# BEACON.net
KiCad netlist of a schematic drawn in EAGLE
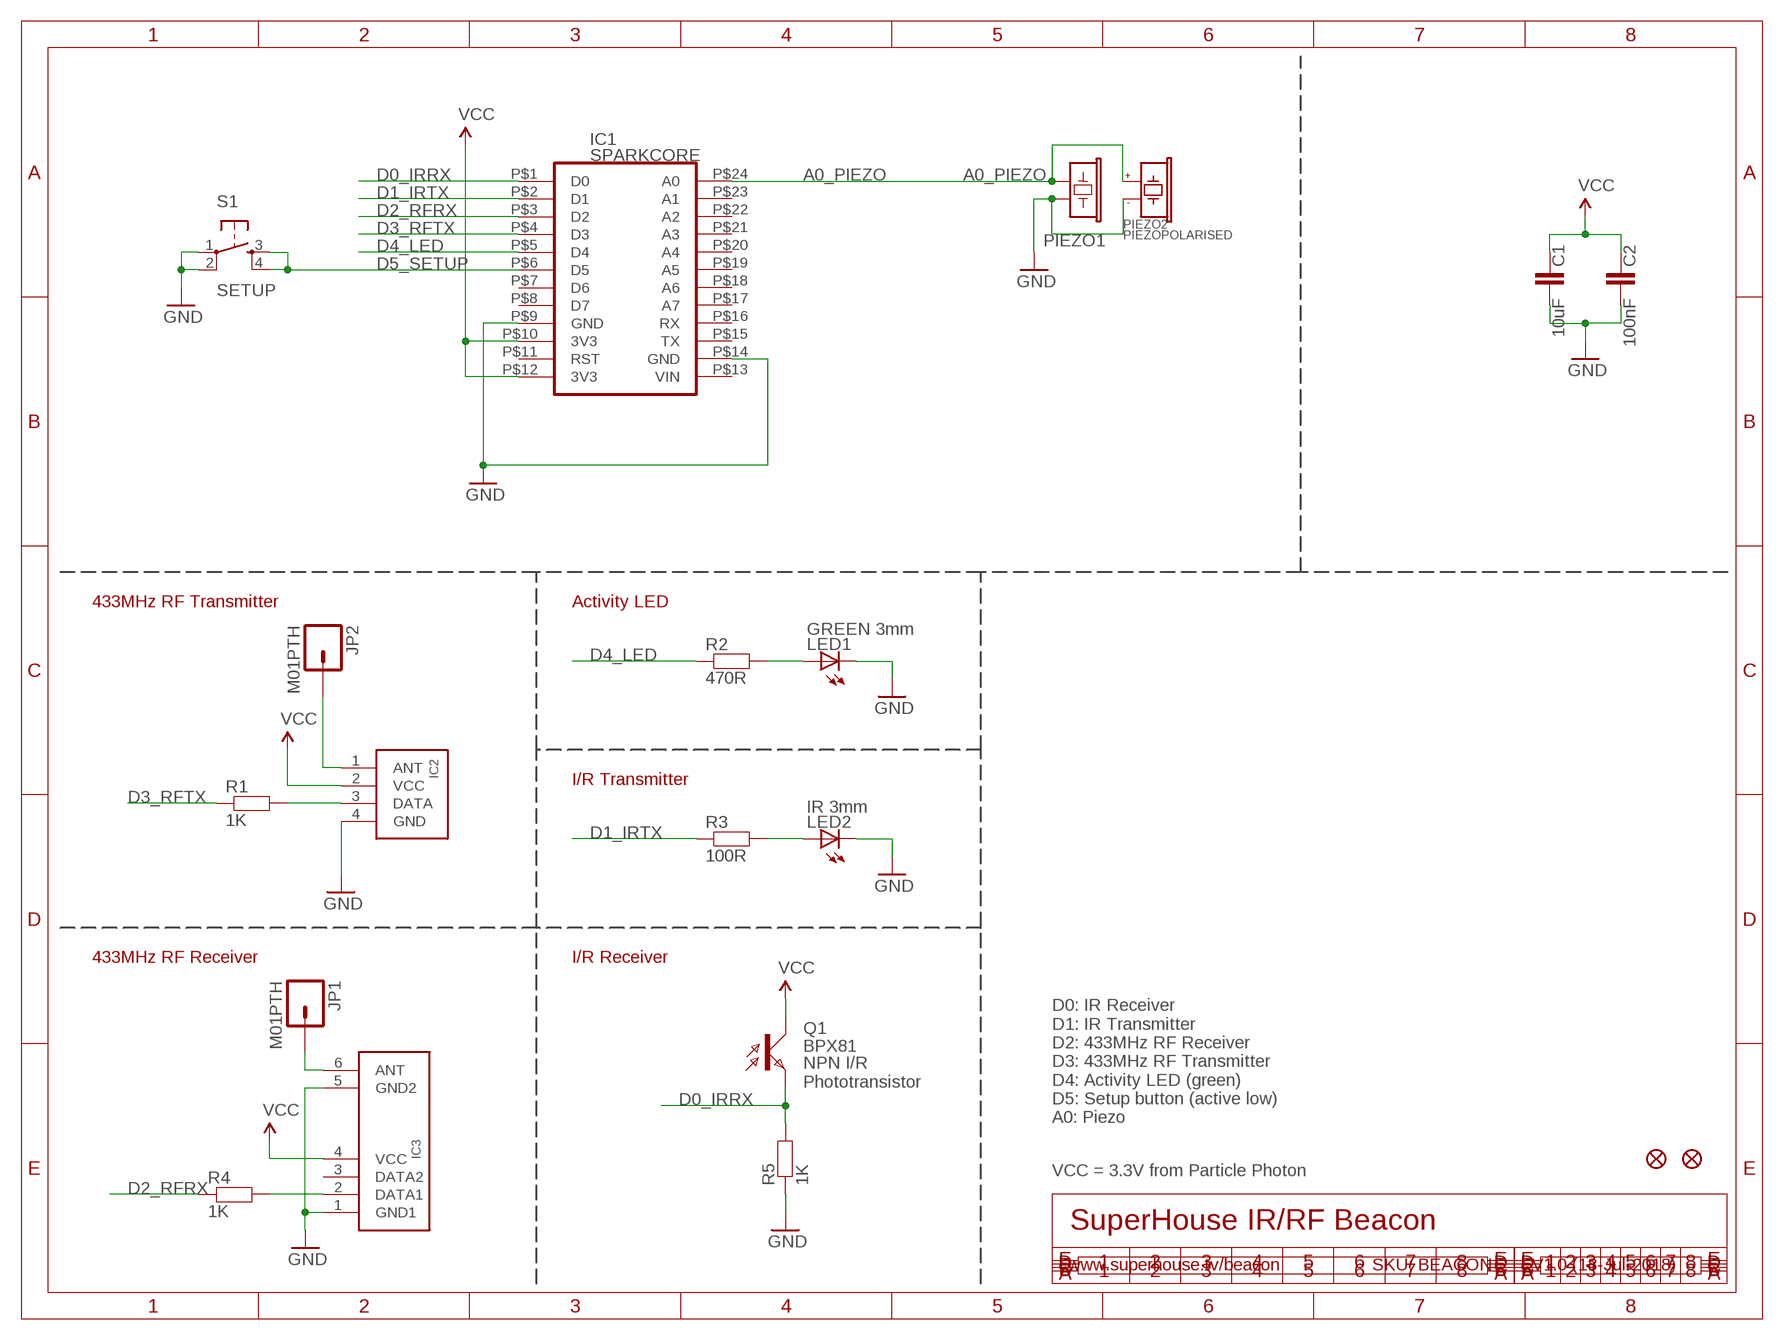
[diagram p0: schematic, sheet 1]

(export (version "E")
  (design (tool "Eeschema 10.0.6"))
  (components
    (comp (ref "C1")
      (value "10uF")
      (footprint "eagle-import:C0805")
      (libsource (lib "eagle-import") (part "C-EUC0805"))
    )
    (comp (ref "C2")
      (value "100nF")
      (footprint "eagle-import:0603")
      (libsource (lib "eagle-import") (part "CAP0603"))
    )
    (comp (ref "IC1")
      (value "SPARKCORE")
      (footprint "eagle-import:SPARKCORE")
      (libsource (lib "eagle-import") (part "SPARKCORE"))
    )
    (comp (ref "IC2")
      (value "TX-C1FLAT")
      (footprint "eagle-import:TX-C1-FLAT")
      (libsource (lib "eagle-import") (part "TX-C1FLAT"))
    )
    (comp (ref "IC3")
      (value "RXB1SHORTFLAT")
      (footprint "eagle-import:RX-B1-SHORT-FLAT")
      (libsource (lib "eagle-import") (part "RXB1SHORTFLAT"))
    )
    (comp (ref "JP1")
      (value "M01PTH")
      (footprint "eagle-import:1X01")
      (libsource (lib "eagle-import") (part "M01PTH"))
    )
    (comp (ref "JP2")
      (value "M01PTH")
      (footprint "eagle-import:1X01")
      (libsource (lib "eagle-import") (part "M01PTH"))
    )
    (comp (ref "LED1")
      (value "GREEN 3mm")
      (footprint "eagle-import:LED3MM")
      (libsource (lib "eagle-import") (part "LED3MM"))
    )
    (comp (ref "LED2")
      (value "IR 3mm")
      (footprint "eagle-import:LED3MM")
      (libsource (lib "eagle-import") (part "LED3MM"))
    )
    (comp (ref "PIEZO1")
      (value "BUZZERSMD12X12")
      (footprint "eagle-import:BUZZER-12X12-SMT")
      (libsource (lib "eagle-import") (part "BUZZERSMD12X12"))
    )
    (comp (ref "PIEZO2")
      (value "PIEZOPOLARISED")
      (footprint "eagle-import:PIEZO12MMWIDEPOLARISED")
      (libsource (lib "eagle-import") (part "PIEZOPOLARISED"))
    )
    (comp (ref "Q1")
      (value "BPX81")
      (footprint "eagle-import:BPX81")
      (libsource (lib "eagle-import") (part "BPX81"))
    )
    (comp (ref "R1")
      (value "1K")
      (footprint "eagle-import:0603")
      (libsource (lib "eagle-import") (part "RESISTOR0603"))
    )
    (comp (ref "R2")
      (value "470R")
      (footprint "eagle-import:0603")
      (libsource (lib "eagle-import") (part "RESISTOR0603"))
    )
    (comp (ref "R3")
      (value "100R")
      (footprint "eagle-import:0603")
      (libsource (lib "eagle-import") (part "RESISTOR0603"))
    )
    (comp (ref "R4")
      (value "1K")
      (footprint "eagle-import:0603")
      (libsource (lib "eagle-import") (part "RESISTOR0603"))
    )
    (comp (ref "R5")
      (value "1K")
      (footprint "eagle-import:0603")
      (libsource (lib "eagle-import") (part "RESISTOR0603"))
    )
    (comp (ref "S1")
      (value "SETUP")
      (footprint "eagle-import:TACTILE-PTH")
      (libsource (lib "eagle-import") (part "TAC_SWITCHPTH"))
    )
    (comp (ref "U$4")
      (value "FIDUCIAL1X2.5")
      (footprint "eagle-import:FIDUCIAL-1X2.5")
      (libsource (lib "eagle-import") (part "FIDUCIAL1X2.5"))
    )
    (comp (ref "U$5")
      (value "FIDUCIAL1X2.5")
      (footprint "eagle-import:FIDUCIAL-1X2.5")
      (libsource (lib "eagle-import") (part "FIDUCIAL1X2.5"))
    )
  )
  (nets
    (net (code "1") (name "/A0_PIEZO") (class "Default")
      (node (ref "IC1") (pin "P$24") (pinfunction "A0_P$24") (pintype "bidirectional"))
      (node (ref "PIEZO1") (pin "1") (pinfunction "1_1") (pintype "passive"))
      (node (ref "PIEZO2") (pin "1") (pinfunction "+_1") (pintype "bidirectional"))
    )
    (net (code "2") (name "/D0_IRRX") (class "Default")
      (node (ref "IC1") (pin "P$1") (pinfunction "D0_P$1") (pintype "bidirectional"))
      (node (ref "Q1") (pin "E") (pinfunction "E_E") (pintype "passive"))
      (node (ref "R5") (pin "2") (pinfunction "2_2") (pintype "passive"))
    )
    (net (code "3") (name "/D1_IRTX") (class "Default")
      (node (ref "IC1") (pin "P$2") (pinfunction "D1_P$2") (pintype "bidirectional"))
      (node (ref "R3") (pin "1") (pinfunction "1_1") (pintype "passive"))
    )
    (net (code "4") (name "/D2_RFRX") (class "Default")
      (node (ref "IC1") (pin "P$3") (pinfunction "D2_P$3") (pintype "bidirectional"))
      (node (ref "R4") (pin "1") (pinfunction "1_1") (pintype "passive"))
    )
    (net (code "5") (name "/D3_RFTX") (class "Default")
      (node (ref "IC1") (pin "P$4") (pinfunction "D3_P$4") (pintype "bidirectional"))
      (node (ref "R1") (pin "1") (pinfunction "1_1") (pintype "passive"))
    )
    (net (code "6") (name "/D4_LED") (class "Default")
      (node (ref "IC1") (pin "P$5") (pinfunction "D4_P$5") (pintype "bidirectional"))
      (node (ref "R2") (pin "1") (pinfunction "1_1") (pintype "passive"))
    )
    (net (code "7") (name "/D5_SETUP") (class "Default")
      (node (ref "IC1") (pin "P$6") (pinfunction "D5_P$6") (pintype "bidirectional"))
      (node (ref "S1") (pin "3") (pinfunction "3_3") (pintype "passive"))
      (node (ref "S1") (pin "4") (pinfunction "4_4") (pintype "passive"))
    )
    (net (code "8") (name "GND") (class "Default")
      (node (ref "C1") (pin "1") (pinfunction "1_1") (pintype "passive"))
      (node (ref "C2") (pin "2") (pinfunction "2_2") (pintype "passive"))
      (node (ref "IC1") (pin "P$14") (pinfunction "GND_P$14") (pintype "bidirectional"))
      (node (ref "IC1") (pin "P$9") (pinfunction "GND_P$9") (pintype "bidirectional"))
      (node (ref "IC2") (pin "4") (pinfunction "GND_4") (pintype "power_in"))
      (node (ref "IC3") (pin "1") (pinfunction "GND1_1") (pintype "bidirectional"))
      (node (ref "IC3") (pin "5") (pinfunction "GND2_5") (pintype "bidirectional"))
      (node (ref "LED1") (pin "K") (pinfunction "C_K") (pintype "passive"))
      (node (ref "LED2") (pin "K") (pinfunction "C_K") (pintype "passive"))
      (node (ref "PIEZO1") (pin "2") (pinfunction "2_2") (pintype "passive"))
      (node (ref "PIEZO2") (pin "2") (pinfunction "-_2") (pintype "bidirectional"))
      (node (ref "R5") (pin "1") (pinfunction "1_1") (pintype "passive"))
      (node (ref "S1") (pin "1") (pinfunction "1_1") (pintype "passive"))
      (node (ref "S1") (pin "2") (pinfunction "2_2") (pintype "passive"))
    )
    (net (code "9") (name "Net-(IC2-ANT)") (class "Default")
      (node (ref "IC2") (pin "1") (pinfunction "ANT_1") (pintype "output"))
      (node (ref "JP2") (pin "1") (pinfunction "1_1") (pintype "passive"))
    )
    (net (code "10") (name "Net-(IC2-DATA)") (class "Default")
      (node (ref "IC2") (pin "3") (pinfunction "DATA_3") (pintype "input"))
      (node (ref "R1") (pin "2") (pinfunction "2_2") (pintype "passive"))
    )
    (net (code "11") (name "Net-(IC3-ANT)") (class "Default")
      (node (ref "IC3") (pin "6") (pinfunction "ANT_6") (pintype "bidirectional"))
      (node (ref "JP1") (pin "1") (pinfunction "1_1") (pintype "passive"))
    )
    (net (code "12") (name "Net-(IC3-DATA1)") (class "Default")
      (node (ref "IC3") (pin "2") (pinfunction "DATA1_2") (pintype "bidirectional"))
      (node (ref "R4") (pin "2") (pinfunction "2_2") (pintype "passive"))
    )
    (net (code "13") (name "Net-(LED1-PadA)") (class "Default")
      (node (ref "LED1") (pin "A") (pinfunction "A_A") (pintype "passive"))
      (node (ref "R2") (pin "2") (pinfunction "2_2") (pintype "passive"))
    )
    (net (code "14") (name "Net-(LED2-PadA)") (class "Default")
      (node (ref "LED2") (pin "A") (pinfunction "A_A") (pintype "passive"))
      (node (ref "R3") (pin "2") (pinfunction "2_2") (pintype "passive"))
    )
    (net (code "15") (name "VCC") (class "Default")
      (node (ref "C1") (pin "2") (pinfunction "2_2") (pintype "passive"))
      (node (ref "C2") (pin "1") (pinfunction "1_1") (pintype "passive"))
      (node (ref "IC1") (pin "P$10") (pinfunction "3V3_P$10") (pintype "bidirectional"))
      (node (ref "IC1") (pin "P$12") (pinfunction "3V3_P$12") (pintype "bidirectional"))
      (node (ref "IC2") (pin "2") (pinfunction "VCC_2") (pintype "power_in"))
      (node (ref "IC3") (pin "4") (pinfunction "VCC_4") (pintype "bidirectional"))
      (node (ref "Q1") (pin "C") (pinfunction "C_C") (pintype "passive"))
    )
    (net (code "16") (name "unconnected-(IC1-A1-PadP$23)") (class "Default")
      (node (ref "IC1") (pin "P$23") (pinfunction "A1_P$23") (pintype "bidirectional"))
    )
    (net (code "17") (name "unconnected-(IC1-A2-PadP$22)") (class "Default")
      (node (ref "IC1") (pin "P$22") (pinfunction "A2_P$22") (pintype "bidirectional"))
    )
    (net (code "18") (name "unconnected-(IC1-A3-PadP$21)") (class "Default")
      (node (ref "IC1") (pin "P$21") (pinfunction "A3_P$21") (pintype "bidirectional"))
    )
    (net (code "19") (name "unconnected-(IC1-A4-PadP$20)") (class "Default")
      (node (ref "IC1") (pin "P$20") (pinfunction "A4_P$20") (pintype "bidirectional"))
    )
    (net (code "20") (name "unconnected-(IC1-A5-PadP$19)") (class "Default")
      (node (ref "IC1") (pin "P$19") (pinfunction "A5_P$19") (pintype "bidirectional"))
    )
    (net (code "21") (name "unconnected-(IC1-A6-PadP$18)") (class "Default")
      (node (ref "IC1") (pin "P$18") (pinfunction "A6_P$18") (pintype "bidirectional"))
    )
    (net (code "22") (name "unconnected-(IC1-A7-PadP$17)") (class "Default")
      (node (ref "IC1") (pin "P$17") (pinfunction "A7_P$17") (pintype "bidirectional"))
    )
    (net (code "23") (name "unconnected-(IC1-D6-PadP$7)") (class "Default")
      (node (ref "IC1") (pin "P$7") (pinfunction "D6_P$7") (pintype "bidirectional"))
    )
    (net (code "24") (name "unconnected-(IC1-D7-PadP$8)") (class "Default")
      (node (ref "IC1") (pin "P$8") (pinfunction "D7_P$8") (pintype "bidirectional"))
    )
    (net (code "25") (name "unconnected-(IC1-RST-PadP$11)") (class "Default")
      (node (ref "IC1") (pin "P$11") (pinfunction "RST_P$11") (pintype "bidirectional"))
    )
    (net (code "26") (name "unconnected-(IC1-RX-PadP$16)") (class "Default")
      (node (ref "IC1") (pin "P$16") (pinfunction "RX_P$16") (pintype "bidirectional"))
    )
    (net (code "27") (name "unconnected-(IC1-TX-PadP$15)") (class "Default")
      (node (ref "IC1") (pin "P$15") (pinfunction "TX_P$15") (pintype "bidirectional"))
    )
    (net (code "28") (name "unconnected-(IC1-VIN-PadP$13)") (class "Default")
      (node (ref "IC1") (pin "P$13") (pinfunction "VIN_P$13") (pintype "bidirectional"))
    )
    (net (code "29") (name "unconnected-(IC3-DATA2-Pad3)") (class "Default")
      (node (ref "IC3") (pin "3") (pinfunction "DATA2_3") (pintype "bidirectional"))
    )
  )
)
